# power_module.net
KiCad netlist of a schematic drawn in EAGLE
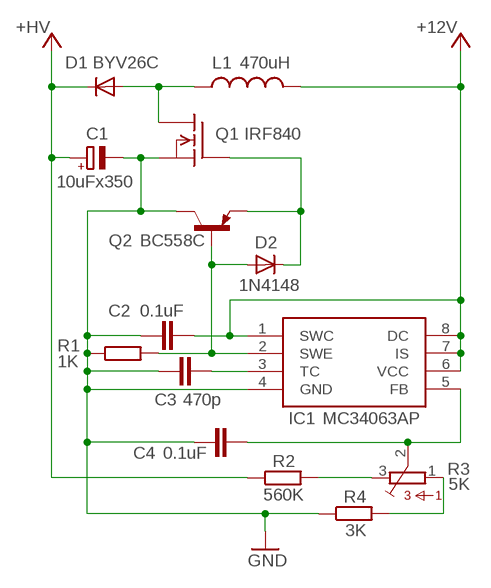
[diagram p0: schematic, sheet 1]

(export (version "E")
  (design (tool "Eeschema 10.0.6"))
  (components
    (comp (ref "C1")
      (value "10uFx350")
      (footprint "eagle-import:E5-10,5")
      (libsource (lib "eagle-import") (part "CPOL-EUE5-10.5"))
    )
    (comp (ref "C2")
      (value "0.1uF")
      (footprint "eagle-import:C102-043X133")
      (libsource (lib "eagle-import") (part "C-EU102-043X133"))
    )
    (comp (ref "C3")
      (value "470p")
      (footprint "eagle-import:C050-035X075")
      (libsource (lib "eagle-import") (part "C-EU050-035X075"))
    )
    (comp (ref "C4")
      (value "0.1uF")
      (footprint "eagle-import:C102-043X133")
      (libsource (lib "eagle-import") (part "C-EU102-043X133"))
    )
    (comp (ref "D1")
      (value "BYV26C")
      (footprint "eagle-import:SOD57-10")
      (libsource (lib "eagle-import") (part "BYV27"))
    )
    (comp (ref "D2")
      (value "1N4148")
      (footprint "eagle-import:DO35-10")
      (libsource (lib "eagle-import") (part "1N4148DO35-10"))
    )
    (comp (ref "IC1")
      (value "MC34063AP")
      (footprint "eagle-import:DIL08")
      (libsource (lib "eagle-import") (part "MC34063AP"))
    )
    (comp (ref "L1")
      (value "470uH")
      (footprint "eagle-import:6000-XXXX-RC")
      (libsource (lib "eagle-import") (part "L-US6000-XXX-RC"))
    )
    (comp (ref "Q1")
      (value "IRF840")
      (footprint "eagle-import:TO220")
      (libsource (lib "eagle-import") (part "IRF840"))
    )
    (comp (ref "Q2")
      (value "BC558C")
      (footprint "eagle-import:TO92-EBC")
      (libsource (lib "eagle-import") (part "BC558C"))
    )
    (comp (ref "R1")
      (value "1K")
      (footprint "eagle-import:0207_10")
      (libsource (lib "eagle-import") (part "R-EU_0207/10"))
    )
    (comp (ref "R2")
      (value "560K")
      (footprint "eagle-import:0207_10")
      (libsource (lib "eagle-import") (part "R-EU_0207/10"))
    )
    (comp (ref "R3")
      (value "5K")
      (footprint "eagle-import:3362P")
      (libsource (lib "eagle-import") (part "3362P"))
    )
    (comp (ref "R4")
      (value "3K")
      (footprint "eagle-import:0207_10")
      (libsource (lib "eagle-import") (part "R-EU_0207/10"))
    )
  )
  (nets
    (net (code "1") (name "+12V") (class "Default")
      (node (ref "C2") (pin "2") (pinfunction "2_2") (pintype "passive"))
      (node (ref "IC1") (pin "1") (pinfunction "SWC_1") (pintype "passive"))
      (node (ref "IC1") (pin "6") (pinfunction "VCC_6") (pintype "passive"))
      (node (ref "IC1") (pin "7") (pinfunction "IS_7") (pintype "passive"))
      (node (ref "IC1") (pin "8") (pinfunction "DC_8") (pintype "passive"))
      (node (ref "L1") (pin "2") (pinfunction "2_2") (pintype "passive"))
    )
    (net (code "2") (name "+HV") (class "Default")
      (node (ref "C1") (pin "+") (pinfunction "+_+") (pintype "passive"))
      (node (ref "D1") (pin "C") (pinfunction "C_C") (pintype "passive"))
      (node (ref "R2") (pin "1") (pinfunction "1_1") (pintype "passive"))
    )
    (net (code "3") (name "GND") (class "Default")
      (node (ref "C1") (pin "-") (pinfunction "-_-") (pintype "passive"))
      (node (ref "C2") (pin "1") (pinfunction "1_1") (pintype "passive"))
      (node (ref "C3") (pin "1") (pinfunction "1_1") (pintype "passive"))
      (node (ref "C4") (pin "1") (pinfunction "1_1") (pintype "passive"))
      (node (ref "IC1") (pin "4") (pinfunction "GND_4") (pintype "passive"))
      (node (ref "Q1") (pin "3") (pinfunction "S_3") (pintype "passive"))
      (node (ref "Q2") (pin "C") (pinfunction "C_C") (pintype "passive"))
      (node (ref "R1") (pin "1") (pinfunction "1_1") (pintype "passive"))
      (node (ref "R4") (pin "1") (pinfunction "1_1") (pintype "passive"))
    )
    (net (code "4") (name "Net-(IC1-FB)") (class "Default")
      (node (ref "C4") (pin "2") (pinfunction "2_2") (pintype "passive"))
      (node (ref "IC1") (pin "5") (pinfunction "FB_5") (pintype "passive"))
      (node (ref "R3") (pin "2") (pinfunction "2_2") (pintype "passive"))
    )
    (net (code "5") (name "Net-(IC1-SWE)") (class "Default")
      (node (ref "D2") (pin "A") (pinfunction "A_A") (pintype "passive"))
      (node (ref "IC1") (pin "2") (pinfunction "SWE_2") (pintype "passive"))
      (node (ref "Q2") (pin "B") (pinfunction "B_B") (pintype "passive"))
      (node (ref "R1") (pin "2") (pinfunction "2_2") (pintype "passive"))
    )
    (net (code "6") (name "Net-(IC1-TC)") (class "Default")
      (node (ref "C3") (pin "2") (pinfunction "2_2") (pintype "passive"))
      (node (ref "IC1") (pin "3") (pinfunction "TC_3") (pintype "passive"))
    )
    (net (code "7") (name "Net-(Q1-D)") (class "Default")
      (node (ref "D1") (pin "A") (pinfunction "A_A") (pintype "passive"))
      (node (ref "L1") (pin "1") (pinfunction "1_1") (pintype "passive"))
      (node (ref "Q1") (pin "2") (pinfunction "D_2") (pintype "passive"))
    )
    (net (code "8") (name "Net-(Q1-G)") (class "Default")
      (node (ref "D2") (pin "C") (pinfunction "C_C") (pintype "passive"))
      (node (ref "Q1") (pin "1") (pinfunction "G_1") (pintype "passive"))
      (node (ref "Q2") (pin "E") (pinfunction "E_E") (pintype "passive"))
    )
    (net (code "9") (name "Net-(R2-Pad2)") (class "Default")
      (node (ref "R2") (pin "2") (pinfunction "2_2") (pintype "passive"))
      (node (ref "R3") (pin "3") (pinfunction "3_3") (pintype "passive"))
    )
    (net (code "10") (name "Net-(R3-Pad1)") (class "Default")
      (node (ref "R3") (pin "1") (pinfunction "1_1") (pintype "passive"))
      (node (ref "R4") (pin "2") (pinfunction "2_2") (pintype "passive"))
    )
  )
)
